# 01_MAIN.net
KiCad netlist of a schematic drawn in Altium Designer
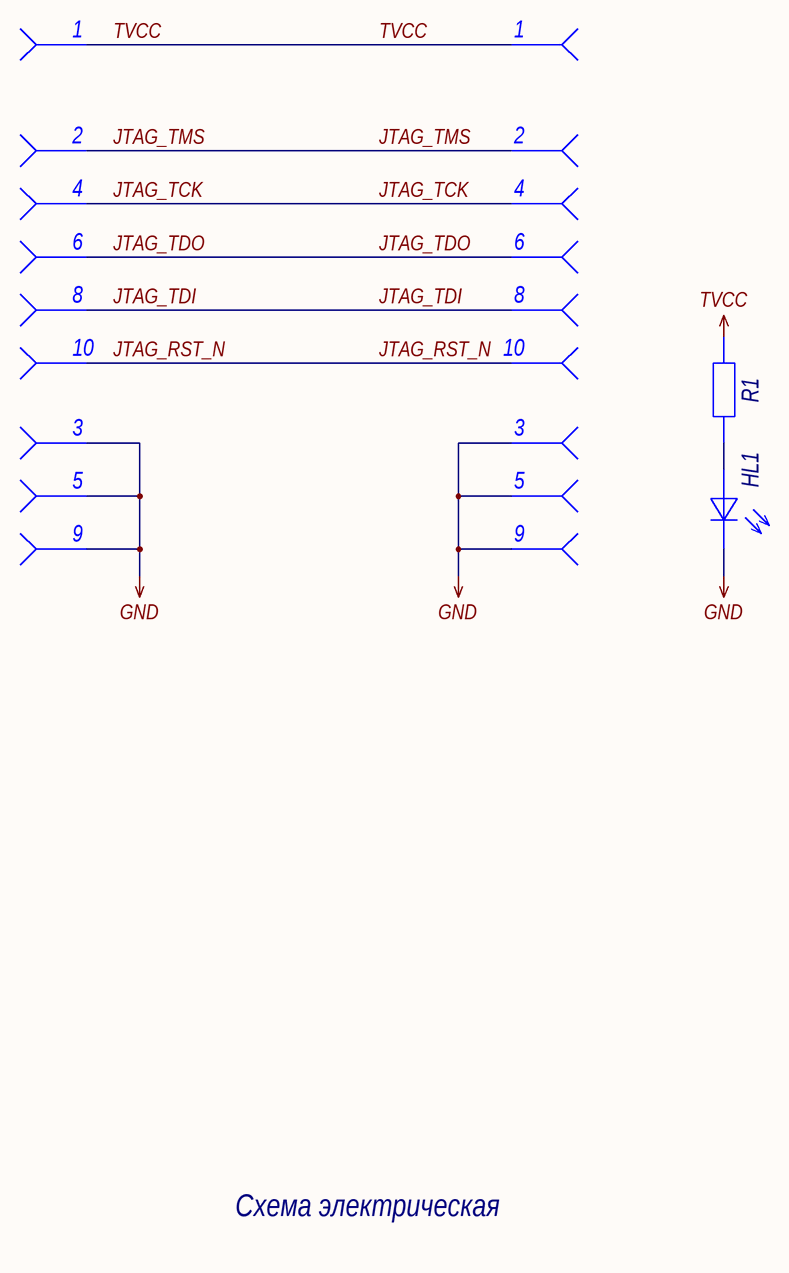
[diagram p0: 01_MAIN.SchDoc]

(export (version "E")
  (design (tool "Eeschema 10.0.6"))
  (components
    (comp (ref "HL1")
      (value "TVCC")
      (footprint "LD0402_L")
      (fields
        (field (name "PART NUMBER") "KPHHS-1005QBC-D-V")
        (field (name "MANUFACTURER") "Kingbright")
        (field (name "PUBLISHER") "Andrew Danich")
      )
      (libsource (lib "ADLib") (part "Led-1"))
    )
    (comp (ref "R1")
      (value "Resistor")
      (footprint "R0402_L")
      (fields
        (field (name "PART NUMBER") "RC0402JR-0710KL")
        (field (name "TOLERANCE") "±5%")
        (field (name "MANUFACTURER") "Yageo")
        (field (name "PUBLISHER") "Andrew Danich")
      )
      (libsource (lib "ADLib") (part "Resistor"))
    )
    (comp (ref "XS1")
      (value "JTAG")
      (footprint "XF2M-1015-1A")
      (fields
        (field (name "PART NUMBER") "XF2M-1015-1A")
        (field (name "MANUFACTURER") "Omron Electronics")
        (field (name "PUBLISHER") "Viktor Klishin")
      )
      (libsource (lib "ADLib") (part "Con-10-F_S"))
    )
    (comp (ref "XS2")
      (value "PBD-10_S")
      (footprint "PBD-10")
      (fields (field (name "PUBLISHER") "Andrew Danich"))
      (libsource (lib "Schlib") (part "PBD-10_S"))
    )
  )
  (nets
    (net (code "1") (name "/JTAG_RST_N") (class "Default")
      (node (ref "XS1") (pin "10") (pintype "passive"))
      (node (ref "XS2") (pin "10") (pintype "passive"))
    )
    (net (code "2") (name "/JTAG_TCK") (class "Default")
      (node (ref "XS1") (pin "4") (pintype "passive"))
      (node (ref "XS2") (pin "4") (pintype "passive"))
    )
    (net (code "3") (name "/JTAG_TDI") (class "Default")
      (node (ref "XS1") (pin "8") (pintype "passive"))
      (node (ref "XS2") (pin "8") (pintype "passive"))
    )
    (net (code "4") (name "/JTAG_TDO") (class "Default")
      (node (ref "XS1") (pin "6") (pintype "passive"))
      (node (ref "XS2") (pin "6") (pintype "passive"))
    )
    (net (code "5") (name "/JTAG_TMS") (class "Default")
      (node (ref "XS1") (pin "2") (pintype "passive"))
      (node (ref "XS2") (pin "2") (pintype "passive"))
    )
    (net (code "6") (name "GND") (class "Default")
      (node (ref "HL1") (pin "2") (pinfunction "К_2") (pintype "passive"))
      (node (ref "XS1") (pin "3") (pintype "passive"))
      (node (ref "XS1") (pin "5") (pintype "passive"))
      (node (ref "XS1") (pin "9") (pintype "passive"))
      (node (ref "XS2") (pin "3") (pintype "passive"))
      (node (ref "XS2") (pin "5") (pintype "passive"))
      (node (ref "XS2") (pin "9") (pintype "passive"))
    )
    (net (code "7") (name "Net-(HL1-А)") (class "Default")
      (node (ref "HL1") (pin "1") (pinfunction "А_1") (pintype "passive"))
      (node (ref "R1") (pin "1") (pinfunction "1_1") (pintype "passive"))
    )
    (net (code "8") (name "TVCC") (class "Default")
      (node (ref "R1") (pin "2") (pinfunction "2_2") (pintype "passive"))
      (node (ref "XS1") (pin "1") (pintype "passive"))
      (node (ref "XS2") (pin "1") (pintype "passive"))
    )
  )
)
